# analog_channel_-_old.net
KiCad netlist of a schematic drawn in Altium Designer
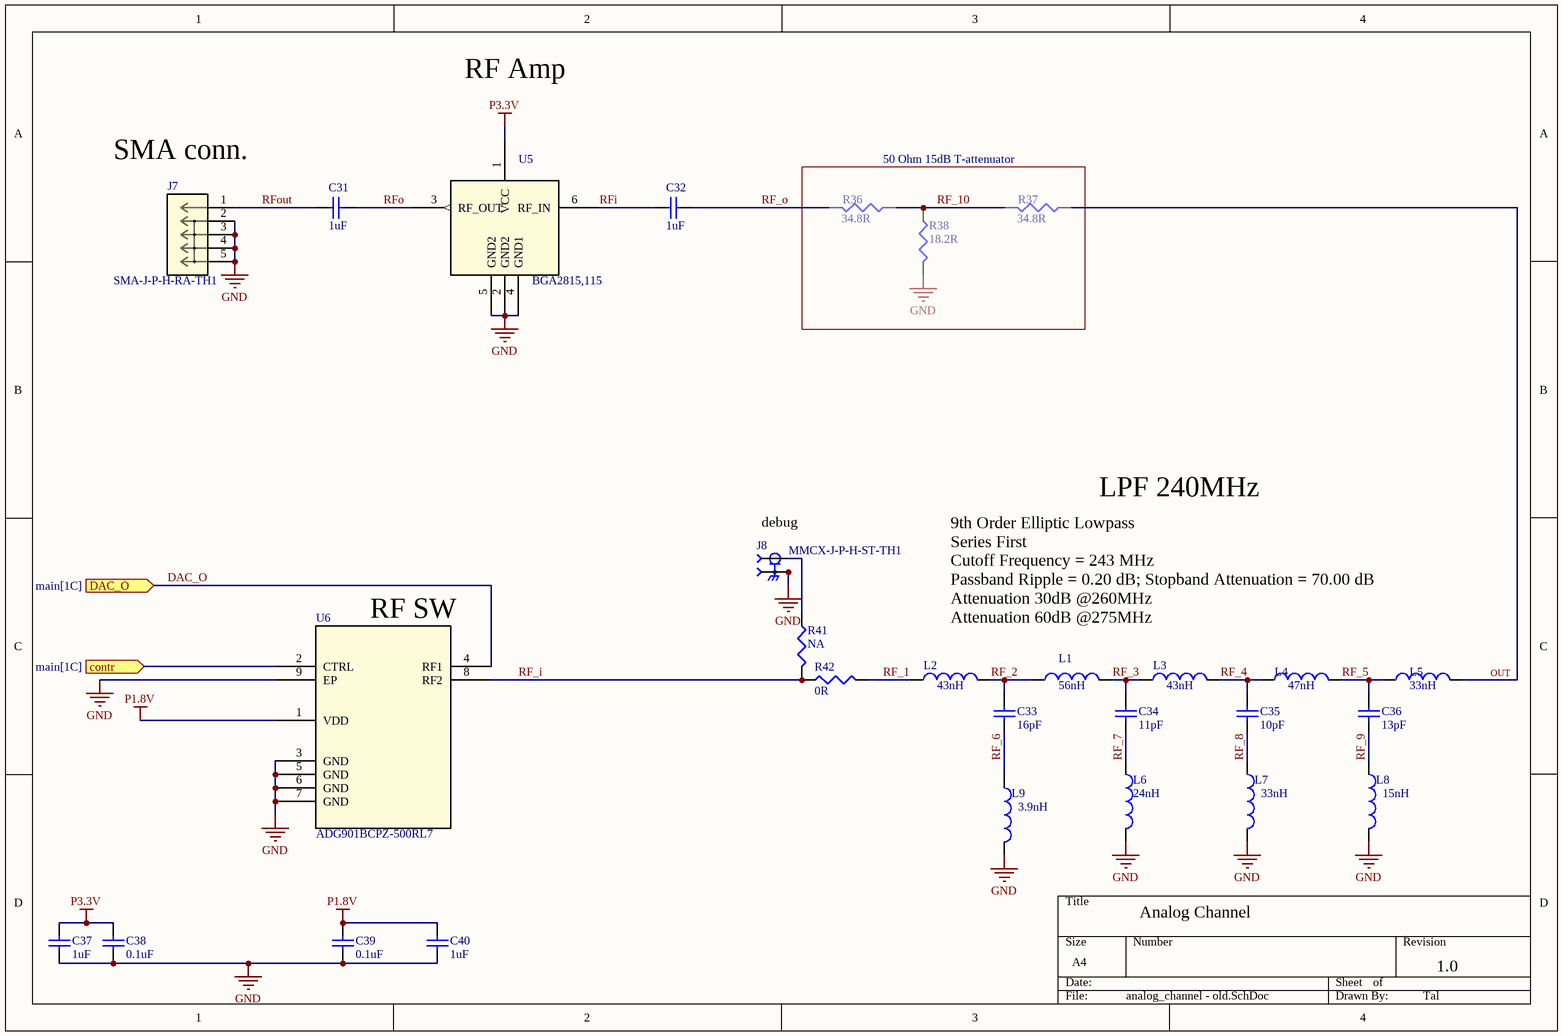
[diagram p0: analog_channel - old.SchDoc]

(export (version "E")
  (design (tool "Eeschema 10.0.6"))
  (components
    (comp (ref "C31")
      (value "1uF 25V")
      (footprint "Landa_PCB:C0402")
      (description "CAP CER 1uF 25V X5R 0402")
      (fields
        (field (name "MANUFACTURER PART NUMBER") "C1005C0G1H6R8D")
        (field (name "MANUFACTURER") "TDK Corporation")
        (field (name "CAPACITANCE") "1uF")
      )
      (libsource (lib "L_SCH_C") (part "CAP CER 6.8pF 50V NP0 0402"))
    )
    (comp (ref "C32")
      (value "1uF 25V")
      (footprint "Landa_PCB:C0402")
      (description "CAP CER 1uF 25V X5R 0402")
      (fields
        (field (name "MANUFACTURER PART NUMBER") "C1005C0G1H6R8D")
        (field (name "MANUFACTURER") "TDK Corporation")
        (field (name "CAPACITANCE") "1uF")
      )
      (libsource (lib "L_SCH_C") (part "CAP CER 6.8pF 50V NP0 0402"))
    )
    (comp (ref "C33")
      (value "16pF 50V")
      (footprint "Landa_PCB:C0402")
      (description "CAP CER 16PF 50V 5% NP0 0402")
      (fields
        (field (name "MANUFACTURER") "TDK Corporation")
        (field (name "MANUFACTURER PART NUMBER") "C1005C0G1H200J")
        (field (name "CAPACITANCE") "16pF")
      )
      (libsource (lib "L_SCH_C") (part "CAP CER 20pF 50V 5% NP0 0402"))
    )
    (comp (ref "C34")
      (value "11pF 50V")
      (footprint "Landa_PCB:C0402")
      (description "CAP CER 11PF 50V 5% NP0 0402")
      (fields
        (field (name "MANUFACTURER") "TDK Corporation")
        (field (name "MANUFACTURER PART NUMBER") "C1005C0G1H200J")
        (field (name "CAPACITANCE") "11pF")
      )
      (libsource (lib "L_SCH_C") (part "CAP CER 20pF 50V 5% NP0 0402"))
    )
    (comp (ref "C35")
      (value "10pF 50V")
      (footprint "Landa_PCB:C0402")
      (description "CAP CER 10PF 50V 5% NP0 0402")
      (fields
        (field (name "MANUFACTURER") "TDK Corporation")
        (field (name "MANUFACTURER PART NUMBER") "C1005C0G1H200J")
        (field (name "CAPACITANCE") "10pF")
      )
      (libsource (lib "L_SCH_C") (part "CAP CER 20pF 50V 5% NP0 0402"))
    )
    (comp (ref "C36")
      (value "13pF 50V")
      (footprint "Landa_PCB:C0402")
      (description "CAP CER 13PF 50V 5% NP0 0402")
      (fields
        (field (name "MANUFACTURER") "TDK Corporation")
        (field (name "MANUFACTURER PART NUMBER") "C1005C0G1H200J")
        (field (name "CAPACITANCE") "13pF")
      )
      (libsource (lib "L_SCH_C") (part "CAP CER 20pF 50V 5% NP0 0402"))
    )
    (comp (ref "C37")
      (value "1uF 25V")
      (footprint "Landa_PCB:C0402")
      (description "CAP CER 1uF 25V X5R 0402")
      (fields
        (field (name "MANUFACTURER PART NUMBER") "C1005C0G1H6R8D")
        (field (name "MANUFACTURER") "TDK Corporation")
        (field (name "CAPACITANCE") "1uF")
      )
      (libsource (lib "L_SCH_C") (part "CAP CER 6.8pF 50V NP0 0402"))
    )
    (comp (ref "C38")
      (value "0.1uF 50V")
      (footprint "Landa_PCB:C0402")
      (description "CAP CER 0.1uF 50V NP0 0402")
      (fields
        (field (name "MANUFACTURER PART NUMBER") "C1005C0G1H6R8D")
        (field (name "MANUFACTURER") "TDK Corporation")
        (field (name "CAPACITANCE") "0.1uF")
      )
      (libsource (lib "L_SCH_C") (part "CAP CER 6.8pF 50V NP0 0402"))
    )
    (comp (ref "C39")
      (value "0.1uF 50V")
      (footprint "Landa_PCB:C0402")
      (description "CAP CER 0.1uF 50V NP0 0402")
      (fields
        (field (name "MANUFACTURER PART NUMBER") "C1005C0G1H6R8D")
        (field (name "MANUFACTURER") "TDK Corporation")
        (field (name "CAPACITANCE") "0.1uF")
      )
      (libsource (lib "L_SCH_C") (part "CAP CER 6.8pF 50V NP0 0402"))
    )
    (comp (ref "C40")
      (value "1uF 25V")
      (footprint "Landa_PCB:C0402")
      (description "CAP CER 1uF 25V X5R 0402")
      (fields
        (field (name "MANUFACTURER PART NUMBER") "C1005C0G1H6R8D")
        (field (name "MANUFACTURER") "TDK Corporation")
        (field (name "CAPACITANCE") "1uF")
      )
      (libsource (lib "L_SCH_C") (part "CAP CER 6.8pF 50V NP0 0402"))
    )
    (comp (ref "J7")
      (value "SMA-J-P-H-RA-TH1")
      (footprint "CONN_SMA-J-P-H-RA-TH1_SAI")
      (description "No Description Available")
      (fields (field (name "COPYRIGHT") "Copyright (C) 2023 Ultra Librarian. All rights reserved."))
      (libsource (lib "SMA-J-P-H-RA-TH1") (part "SMA-J-P-H-RA-TH1"))
    )
    (comp (ref "J8")
      (value "MMCX-J-P-H-ST-TH1")
      (footprint "SAMTEC_MMCX-J-P-H-ST-TH1")
      (description "MMCX STRAIGHT, THROUGH HOLE JACK- 50 OHM")
      (fields (field (name "MF") "Samtec"))
      (libsource (lib "MMCX-J-P-H-ST-TH1") (part "MMCX-J-P-H-ST-TH1"))
    )
    (comp (ref "L1")
      (value "56nH")
      (footprint "0402-A")
      (description "Inductor")
      (fields (field (name "PUBLISHER") "Altium Limited"))
      (libsource (lib "Miscellaneous Devices") (part "Inductor"))
    )
    (comp (ref "L2")
      (value "43nH")
      (footprint "0402-A")
      (description "Inductor")
      (fields (field (name "PUBLISHER") "Altium Limited"))
      (libsource (lib "Miscellaneous Devices") (part "Inductor"))
    )
    (comp (ref "L3")
      (value "43nH")
      (footprint "0402-A")
      (description "Inductor")
      (fields (field (name "PUBLISHER") "Altium Limited"))
      (libsource (lib "Miscellaneous Devices") (part "Inductor"))
    )
    (comp (ref "L4")
      (value "47nH")
      (footprint "0402-A")
      (description "Inductor")
      (fields (field (name "PUBLISHER") "Altium Limited"))
      (libsource (lib "Miscellaneous Devices") (part "Inductor"))
    )
    (comp (ref "L5")
      (value "33nH")
      (footprint "0402-A")
      (description "Inductor")
      (fields (field (name "PUBLISHER") "Altium Limited"))
      (libsource (lib "Miscellaneous Devices") (part "Inductor"))
    )
    (comp (ref "L6")
      (value "24nH")
      (footprint "0402-A")
      (description "Inductor")
      (fields (field (name "PUBLISHER") "Altium Limited"))
      (libsource (lib "Miscellaneous Devices") (part "Inductor"))
    )
    (comp (ref "L7")
      (value "33nH")
      (footprint "0402-A")
      (description "Inductor")
      (fields (field (name "PUBLISHER") "Altium Limited"))
      (libsource (lib "Miscellaneous Devices") (part "Inductor"))
    )
    (comp (ref "L8")
      (value "15nH")
      (footprint "0402-A")
      (description "Inductor")
      (fields (field (name "PUBLISHER") "Altium Limited"))
      (libsource (lib "Miscellaneous Devices") (part "Inductor"))
    )
    (comp (ref "L9")
      (value "3.9nH")
      (footprint "0402-A")
      (description "Inductor")
      (fields (field (name "PUBLISHER") "Altium Limited"))
      (libsource (lib "Miscellaneous Devices") (part "Inductor"))
    )
    (comp (ref "R36")
      (value "34.8R")
      (footprint "r0402")
      (description "RES 34.8 OHM 1/10W 1% 0402 SMD")
      (fields
        (field (name "MANUFACTURER PART NUMBER") "ERJ-2RKF1000X")
        (field (name "MANUFACTURER") "Panasonic Electronic Components")
      )
      (libsource (lib "L_SCH_R") (part "RES 100 OHM 1/10W 1% 0402 SMD"))
    )
    (comp (ref "R37")
      (value "34.8R")
      (footprint "r0402")
      (description "RES 34.8 OHM 1/10W 1% 0402 SMD")
      (fields
        (field (name "MANUFACTURER PART NUMBER") "ERJ-2RKF1000X")
        (field (name "MANUFACTURER") "Panasonic Electronic Components")
      )
      (libsource (lib "L_SCH_R") (part "RES 100 OHM 1/10W 1% 0402 SMD"))
    )
    (comp (ref "R38")
      (value "18.2R")
      (footprint "r0402")
      (description "RES 18.2 OHM 1/10W 1% 0402 SMD")
      (fields
        (field (name "MANUFACTURER PART NUMBER") "ERJ-2RKF1000X")
        (field (name "MANUFACTURER") "Panasonic Electronic Components")
      )
      (libsource (lib "L_SCH_R") (part "RES 100 OHM 1/10W 1% 0402 SMD"))
    )
    (comp (ref "R41")
      (value "NA")
      (footprint "r0402")
      (description "RES 0 OHM 1/10W 1% 0402 SMD")
      (fields
        (field (name "MANUFACTURER PART NUMBER") "ERJ-2RKF1000X")
        (field (name "MANUFACTURER") "Panasonic Electronic Components")
      )
      (libsource (lib "L_SCH_R") (part "RES 100 OHM 1/10W 1% 0402 SMD"))
    )
    (comp (ref "R42")
      (value "0R")
      (footprint "r0402")
      (description "RES 0 OHM 1/10W 1% 0402 SMD")
      (fields
        (field (name "MANUFACTURER PART NUMBER") "ERJ-2RKF1000X")
        (field (name "MANUFACTURER") "Panasonic Electronic Components")
      )
      (libsource (lib "L_SCH_R") (part "RES 100 OHM 1/10W 1% 0402 SMD"))
    )
    (comp (ref "U5")
      (value "BGA2815,115")
      (footprint "SOT_2815,115_NXP")
      (description "No Description Available")
      (fields (field (name "COPYRIGHT") "Copyright (C) 2023 Ultra Librarian. All rights reserved."))
      (libsource (lib "BGA2815,115") (part "BGA2815,115"))
    )
    (comp (ref "U6")
      (value "ADG901BCPZ-500RL7")
      (footprint "CP_8_2_ADI")
      (description "No Description Available")
      (fields (field (name "COPYRIGHT") "Copyright (C) 2023 Ultra Librarian. All rights reserved."))
      (libsource (lib "ADG901BCPZ-500RL7") (part "ADG901BCPZ-500RL7"))
    )
  )
  (nets
    (net (code "1") (name "/DAC_O") (class "Default")
      (node (ref "U6") (pin "4") (pinfunction "RF1_4") (pintype "passive"))
    )
    (net (code "2") (name "/OUT") (class "Default")
      (node (ref "L5") (pin "2") (pinfunction "2_2") (pintype "passive"))
      (node (ref "R37") (pin "1") (pinfunction "1_1") (pintype "passive"))
    )
    (net (code "3") (name "/RF_1") (class "Default")
      (node (ref "L2") (pin "1") (pinfunction "1_1") (pintype "passive"))
      (node (ref "R42") (pin "2") (pinfunction "2_2") (pintype "passive"))
    )
    (net (code "4") (name "/RF_2") (class "Default")
      (node (ref "C33") (pin "1") (pinfunction "1_1") (pintype "passive"))
      (node (ref "L1") (pin "1") (pinfunction "1_1") (pintype "passive"))
      (node (ref "L2") (pin "2") (pinfunction "2_2") (pintype "passive"))
    )
    (net (code "5") (name "/RF_3") (class "Default")
      (node (ref "C34") (pin "1") (pinfunction "1_1") (pintype "passive"))
      (node (ref "L1") (pin "2") (pinfunction "2_2") (pintype "passive"))
      (node (ref "L3") (pin "1") (pinfunction "1_1") (pintype "passive"))
    )
    (net (code "6") (name "/RF_4") (class "Default")
      (node (ref "C35") (pin "1") (pinfunction "1_1") (pintype "passive"))
      (node (ref "L3") (pin "2") (pinfunction "2_2") (pintype "passive"))
      (node (ref "L4") (pin "1") (pinfunction "1_1") (pintype "passive"))
    )
    (net (code "7") (name "/RF_5") (class "Default")
      (node (ref "C36") (pin "1") (pinfunction "1_1") (pintype "passive"))
      (node (ref "L4") (pin "2") (pinfunction "2_2") (pintype "passive"))
      (node (ref "L5") (pin "1") (pinfunction "1_1") (pintype "passive"))
    )
    (net (code "8") (name "/RF_6") (class "Default")
      (node (ref "C33") (pin "2") (pinfunction "2_2") (pintype "passive"))
      (node (ref "L9") (pin "1") (pinfunction "1_1") (pintype "passive"))
    )
    (net (code "9") (name "/RF_7") (class "Default")
      (node (ref "C34") (pin "2") (pinfunction "2_2") (pintype "passive"))
      (node (ref "L6") (pin "1") (pinfunction "1_1") (pintype "passive"))
    )
    (net (code "10") (name "/RF_8") (class "Default")
      (node (ref "C35") (pin "2") (pinfunction "2_2") (pintype "passive"))
      (node (ref "L7") (pin "1") (pinfunction "1_1") (pintype "passive"))
    )
    (net (code "11") (name "/RF_9") (class "Default")
      (node (ref "C36") (pin "2") (pinfunction "2_2") (pintype "passive"))
      (node (ref "L8") (pin "1") (pinfunction "1_1") (pintype "passive"))
    )
    (net (code "12") (name "/RF_10") (class "Default")
      (node (ref "R36") (pin "1") (pinfunction "1_1") (pintype "passive"))
      (node (ref "R37") (pin "2") (pinfunction "2_2") (pintype "passive"))
      (node (ref "R38") (pin "1") (pinfunction "1_1") (pintype "passive"))
    )
    (net (code "13") (name "/RF_i") (class "Default")
      (node (ref "R41") (pin "2") (pinfunction "2_2") (pintype "passive"))
      (node (ref "R42") (pin "1") (pinfunction "1_1") (pintype "passive"))
      (node (ref "U6") (pin "8") (pinfunction "RF2_8") (pintype "passive"))
    )
    (net (code "14") (name "/RF_o") (class "Default")
      (node (ref "C32") (pin "2") (pinfunction "2_2") (pintype "passive"))
      (node (ref "R36") (pin "2") (pinfunction "2_2") (pintype "passive"))
    )
    (net (code "15") (name "/RFi") (class "Default")
      (node (ref "C32") (pin "1") (pinfunction "1_1") (pintype "passive"))
      (node (ref "U5") (pin "6") (pinfunction "RF_IN_6") (pintype "passive"))
    )
    (net (code "16") (name "/RFo") (class "Default")
      (node (ref "C31") (pin "2") (pinfunction "2_2") (pintype "passive"))
      (node (ref "U5") (pin "3") (pinfunction "RF_OUT_3") (pintype "output"))
    )
    (net (code "17") (name "/RFout") (class "Default")
      (node (ref "C31") (pin "1") (pinfunction "1_1") (pintype "passive"))
      (node (ref "J7") (pin "1") (pinfunction "1_1") (pintype "passive"))
    )
    (net (code "18") (name "/contr") (class "Default")
      (node (ref "U6") (pin "2") (pinfunction "CTRL_2") (pintype "passive"))
    )
    (net (code "19") (name "GND") (class "Default")
      (node (ref "C37") (pin "1") (pinfunction "1_1") (pintype "passive"))
      (node (ref "C38") (pin "1") (pinfunction "1_1") (pintype "passive"))
      (node (ref "C39") (pin "1") (pinfunction "1_1") (pintype "passive"))
      (node (ref "C40") (pin "1") (pinfunction "1_1") (pintype "passive"))
      (node (ref "J7") (pin "2") (pinfunction "2_2") (pintype "passive"))
      (node (ref "J7") (pin "3") (pinfunction "3_3") (pintype "passive"))
      (node (ref "J7") (pin "4") (pinfunction "4_4") (pintype "passive"))
      (node (ref "J7") (pin "5") (pinfunction "5_5") (pintype "passive"))
      (node (ref "J8") (pin "S1") (pinfunction "2_S1") (pintype "passive"))
      (node (ref "J8") (pin "S2") (pinfunction "2_S2") (pintype "passive"))
      (node (ref "J8") (pin "S3") (pinfunction "2_S3") (pintype "passive"))
      (node (ref "J8") (pin "S4") (pinfunction "2_S4") (pintype "passive"))
      (node (ref "L6") (pin "2") (pinfunction "2_2") (pintype "passive"))
      (node (ref "L7") (pin "2") (pinfunction "2_2") (pintype "passive"))
      (node (ref "L8") (pin "2") (pinfunction "2_2") (pintype "passive"))
      (node (ref "L9") (pin "2") (pinfunction "2_2") (pintype "passive"))
      (node (ref "R38") (pin "2") (pinfunction "2_2") (pintype "passive"))
      (node (ref "U5") (pin "2") (pinfunction "GND2_2") (pintype "passive"))
      (node (ref "U5") (pin "4") (pinfunction "GND1_4") (pintype "passive"))
      (node (ref "U5") (pin "5") (pinfunction "GND2_5") (pintype "passive"))
      (node (ref "U6") (pin "3") (pinfunction "GND_3") (pintype "passive"))
      (node (ref "U6") (pin "5") (pinfunction "GND_5") (pintype "passive"))
      (node (ref "U6") (pin "6") (pinfunction "GND_6") (pintype "passive"))
      (node (ref "U6") (pin "7") (pinfunction "GND_7") (pintype "passive"))
      (node (ref "U6") (pin "9") (pinfunction "EP_9") (pintype "passive"))
    )
    (net (code "20") (name "Net-(J8-Pad1)") (class "Default")
      (node (ref "J8") (pin "1") (pinfunction "1_1") (pintype "passive"))
      (node (ref "R41") (pin "1") (pinfunction "1_1") (pintype "passive"))
    )
    (net (code "21") (name "P1.8V") (class "Default")
      (node (ref "C39") (pin "2") (pinfunction "2_2") (pintype "passive"))
      (node (ref "C40") (pin "2") (pinfunction "2_2") (pintype "passive"))
      (node (ref "U6") (pin "1") (pinfunction "VDD_1") (pintype "power_in"))
    )
    (net (code "22") (name "P3.3V") (class "Default")
      (node (ref "C37") (pin "2") (pinfunction "2_2") (pintype "passive"))
      (node (ref "C38") (pin "2") (pinfunction "2_2") (pintype "passive"))
      (node (ref "U5") (pin "1") (pinfunction "VCC_1") (pintype "power_in"))
    )
  )
)
